# AdaptWing.net
KiCad netlist of a schematic drawn in Altium Designer
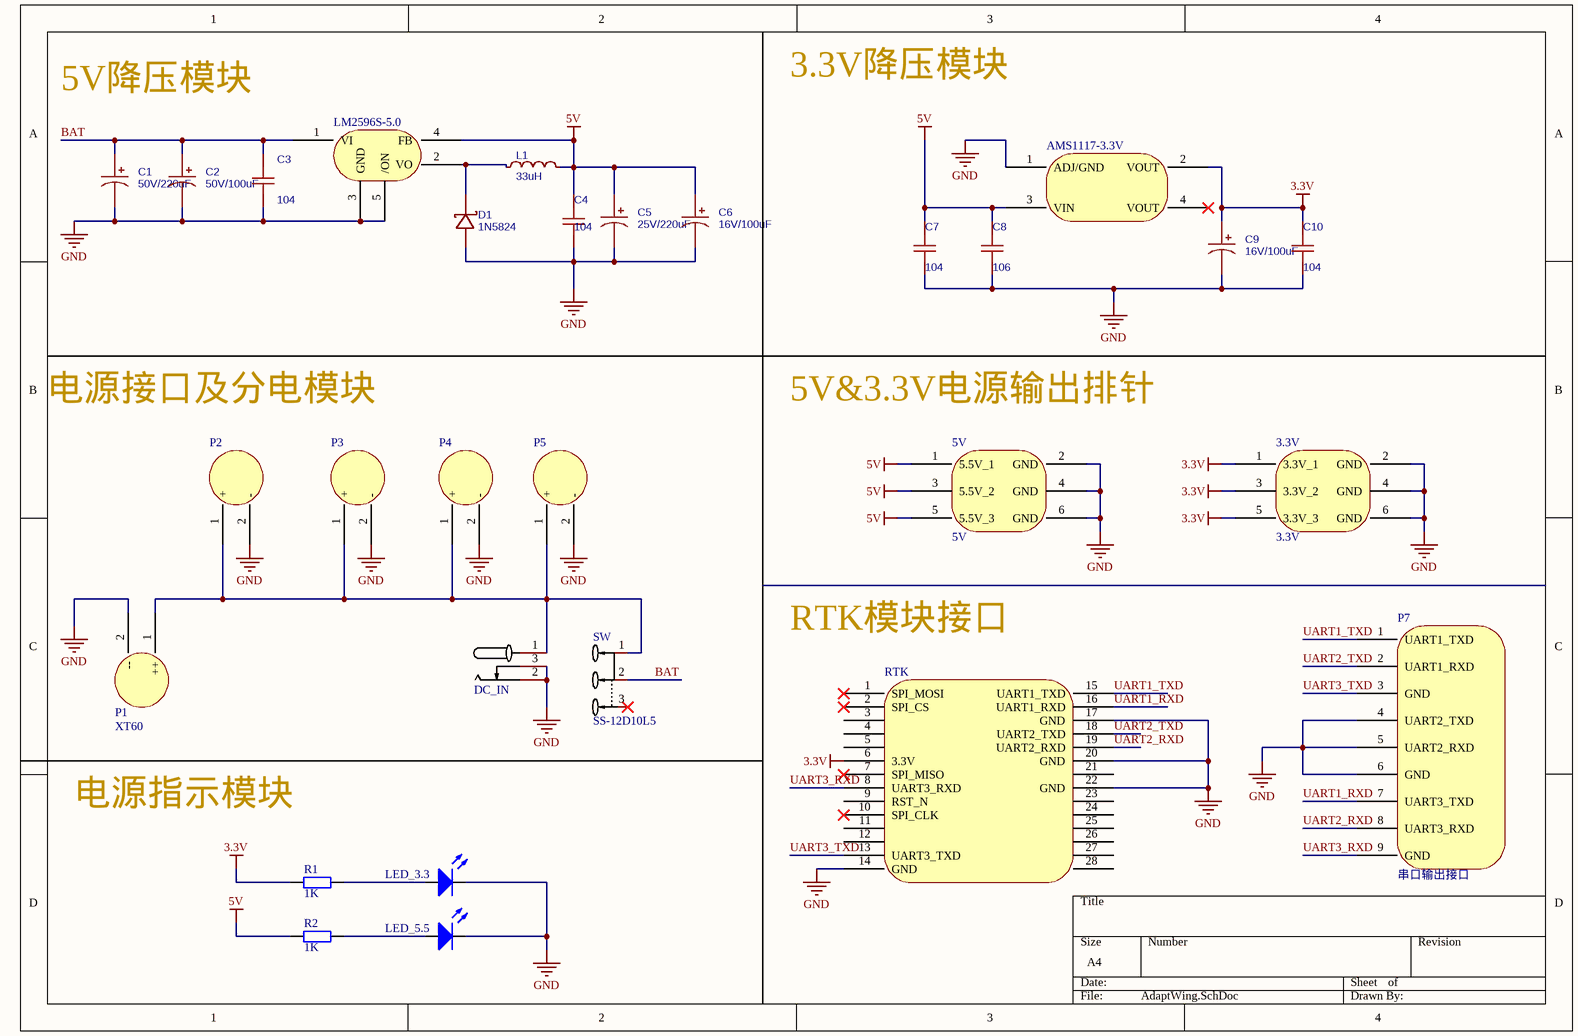
[diagram p0: AdaptWing.SchDoc]

(export (version "E")
  (design (tool "Eeschema 10.0.6"))
  (components
    (comp (ref "3.3V")
      (value "3.3V")
      (footprint "HDR-TH_6P-P2.54-V-M-R2-C3-S2.54-1")
      (libsource (lib "AdaptWing") (part "3.3V"))
    )
    (comp (ref "5V")
      (value "5V")
      (footprint "HDR-TH_6P-P2.54-V-M-R2-C3-S2.54-1")
      (libsource (lib "AdaptWing") (part "5V"))
    )
    (comp (ref "AMS1117-3.3V")
      (value "AMS1117-3.3V")
      (footprint "SOT-223-4_L6.5-W3.5-P2.30-LS7.0-BR")
      (description "3.3V稳压芯片")
      (libsource (lib "AdaptWing") (part "AMS1117-3.3V"))
    )
    (comp (ref "C1")
      (value "50V/220uF")
      (footprint "CAP-SMD_BD8.0-L8.3-W8.3-FD")
      (fields
        (field (name "BOM_SUPPLIER PART") "C525429")
        (field (name "BOM_MANUFACTURER PART") "ECG1KM470F14OTBO")
        (field (name "CONTRIBUTOR") "LCSC")
      )
      (libsource (lib "AdaptWing") (part "50V/220uF"))
    )
    (comp (ref "C2")
      (value "50V/100uF")
      (footprint "CAP-SMD_BD8.0-L8.3-W8.3-FD")
      (fields
        (field (name "BOM_SUPPLIER PART") "C525429")
        (field (name "BOM_MANUFACTURER PART") "ECG1KM470F14OTBO")
        (field (name "CONTRIBUTOR") "LCSC")
      )
      (libsource (lib "AdaptWing") (part "50V/100uF"))
    )
    (comp (ref "C3")
      (value "104")
      (footprint "C0603")
      (fields (field (name "CONTRIBUTOR") "LCEDA_Lib"))
      (libsource (lib "AdaptWing") (part "104"))
    )
    (comp (ref "C4")
      (value "104")
      (footprint "C0603")
      (fields (field (name "CONTRIBUTOR") "LCEDA_Lib"))
      (libsource (lib "AdaptWing") (part "104"))
    )
    (comp (ref "C5")
      (value "25V/220uF")
      (footprint "CAP-SMD_BD6.3-L6.6-W6.6-LS7.4-FD")
      (fields
        (field (name "BOM_SUPPLIER PART") "C525429")
        (field (name "BOM_MANUFACTURER PART") "ECG1KM470F14OTBO")
        (field (name "CONTRIBUTOR") "LCSC")
      )
      (libsource (lib "AdaptWing") (part "25V/220uF"))
    )
    (comp (ref "C6")
      (value "16V/100uF")
      (footprint "CAP-SMD_BD6.3-L6.6-W6.6-FD")
      (description "电解电容")
      (fields
        (field (name "BOM_SUPPLIER PART") "C525429")
        (field (name "BOM_MANUFACTURER PART") "ECG1KM470F14OTBO")
        (field (name "CONTRIBUTOR") "LCSC")
      )
      (libsource (lib "AdaptWing") (part "16V/100uF"))
    )
    (comp (ref "C7")
      (value "104")
      (footprint "C0603")
      (fields (field (name "CONTRIBUTOR") "LCEDA_Lib"))
      (libsource (lib "AdaptWing") (part "104"))
    )
    (comp (ref "C8")
      (value "106")
      (footprint "C0603")
      (fields (field (name "CONTRIBUTOR") "LCEDA_Lib"))
      (libsource (lib "AdaptWing") (part "106"))
    )
    (comp (ref "C9")
      (value "16V/100uF")
      (footprint "CAP-SMD_BD6.3-L6.6-W6.6-FD")
      (description "电解电容")
      (fields
        (field (name "BOM_SUPPLIER PART") "C525429")
        (field (name "BOM_MANUFACTURER PART") "ECG1KM470F14OTBO")
        (field (name "CONTRIBUTOR") "LCSC")
      )
      (libsource (lib "AdaptWing") (part "16V/100uF"))
    )
    (comp (ref "C10")
      (value "104")
      (footprint "C0603")
      (fields (field (name "CONTRIBUTOR") "LCEDA_Lib"))
      (libsource (lib "AdaptWing") (part "104"))
    )
    (comp (ref "D1")
      (value "1N5824")
      (footprint "1N5824")
      (fields (field (name "CONTRIBUTOR") "xuncikulv"))
      (libsource (lib "AdaptWing") (part "1N5824"))
    )
    (comp (ref "DC_IN")
      (value "DC插座")
      (footprint "DC-IN-TH_DC-044-BXXX")
      (libsource (lib "AdaptWing") (part "DC插座"))
    )
    (comp (ref "L1")
      (value "33uH")
      (footprint "1040电感")
      (fields
        (field (name "BOM_SUPPLIER PART") "C268399")
        (field (name "BOM_MANUFACTURER PART") "MPCA-0630-1R0-M")
        (field (name "CONTRIBUTOR") "liuliubilc")
      )
      (libsource (lib "AdaptWing") (part "33uH"))
    )
    (comp (ref "LED_3.3")
      (value "LED_3.3")
      (footprint "0603_LED")
      (description "LED_3.3，使用绿色LED")
      (libsource (lib "AdaptWing") (part "LED_3.3"))
    )
    (comp (ref "LED_5.5")
      (value "LED_5.5")
      (footprint "0603_LED")
      (description "LED_5.5，使用蓝色LED")
      (libsource (lib "AdaptWing") (part "LED_5.5"))
    )
    (comp (ref "LM2596S-5.0")
      (value "LM2596S-5.0")
      (footprint "TO263-5A")
      (description "5V稳压")
      (libsource (lib "AdaptWing") (part "LM2596S-5.0"))
    )
    (comp (ref "P1")
      (value "XT60")
      (footprint "分电焊盘")
      (description "航模电池接口")
      (libsource (lib "AdaptWing") (part "XT60"))
    )
    (comp (ref "P2") (value "分电焊盘") (footprint "分电焊盘") (libsource (lib "AdaptWing") (part "PWR_DIV")))
    (comp (ref "P3") (value "分电焊盘") (footprint "分电焊盘") (libsource (lib "AdaptWing") (part "PWR_DIV")))
    (comp (ref "P4") (value "分电焊盘") (footprint "分电焊盘") (libsource (lib "AdaptWing") (part "PWR_DIV")))
    (comp (ref "P5") (value "分电焊盘") (footprint "分电焊盘") (libsource (lib "AdaptWing") (part "PWR_DIV")))
    (comp (ref "P7")
      (value "串口输出接口")
      (footprint "2.54mm-3×3p")
      (libsource (lib "AdaptWing") (part "2.54mm-3×3p"))
    )
    (comp (ref "R1")
      (value "1K")
      (footprint "0603C")
      (description "Resistor")
      (fields (field (name "PUBLISHER") "Altium Limited"))
      (libsource (lib "AdaptWing") (part "1K"))
    )
    (comp (ref "R2")
      (value "1K")
      (footprint "0603C")
      (description "Resistor")
      (fields (field (name "PUBLISHER") "Altium Limited"))
      (libsource (lib "AdaptWing") (part "1K"))
    )
    (comp (ref "RTK")
      (value "排母2.0mm")
      (footprint "2mm-28pins")
      (libsource (lib "AdaptWing") (part "排母2.0mm"))
    )
    (comp (ref "SW")
      (value "SS-12D10L5")
      (footprint "SW-TH_SS-12D10L5")
      (description "两档滑动开关")
      (fields (field (name "MANUFACTURER") "XKB Connectivity(中国星坤)") (field (name "NAME") "SS-12D10L5"))
      (libsource (lib "AdaptWing") (part "SS-12D10L5"))
    )
  )
  (nets
    (net (code "1") (name "/BAT") (class "Default")
      (node (ref "C1") (pin "1") (pinfunction "1_1") (pintype "passive"))
      (node (ref "C2") (pin "1") (pinfunction "1_1") (pintype "passive"))
      (node (ref "C3") (pin "2") (pinfunction "2_2") (pintype "passive"))
      (node (ref "LM2596S-5.0") (pin "1") (pinfunction "VI_1") (pintype "passive"))
      (node (ref "SW") (pin "2") (pinfunction "2_2") (pintype "passive"))
    )
    (net (code "2") (name "/UART1_RXD") (class "Default")
      (node (ref "P7") (pin "7") (pinfunction "UART3_TXD_7") (pintype "passive"))
      (node (ref "RTK") (pin "16") (pinfunction "UART1_RXD_16") (pintype "passive"))
    )
    (net (code "3") (name "/UART1_TXD") (class "Default")
      (node (ref "P7") (pin "1") (pinfunction "UART1_TXD_1") (pintype "passive"))
      (node (ref "RTK") (pin "15") (pinfunction "UART1_TXD_15") (pintype "passive"))
    )
    (net (code "4") (name "/UART2_RXD") (class "Default")
      (node (ref "P7") (pin "8") (pinfunction "UART3_RXD_8") (pintype "passive"))
      (node (ref "RTK") (pin "19") (pinfunction "UART2_RXD_19") (pintype "passive"))
    )
    (net (code "5") (name "/UART2_TXD") (class "Default")
      (node (ref "P7") (pin "2") (pinfunction "UART1_RXD_2") (pintype "passive"))
      (node (ref "RTK") (pin "18") (pinfunction "UART2_TXD_18") (pintype "passive"))
    )
    (net (code "6") (name "/UART3_RXD") (class "Default")
      (node (ref "P7") (pin "9") (pinfunction "GND_9") (pintype "passive"))
      (node (ref "RTK") (pin "8") (pinfunction "UART3_RXD_8") (pintype "passive"))
    )
    (net (code "7") (name "/UART3_TXD") (class "Default")
      (node (ref "P7") (pin "3") (pinfunction "GND_3") (pintype "passive"))
      (node (ref "RTK") (pin "13") (pinfunction "UART3_TXD_13") (pintype "passive"))
    )
    (net (code "8") (name "3.3V") (class "Default")
      (node (ref "3.3V") (pin "1") (pinfunction "3.3V_1_1") (pintype "passive"))
      (node (ref "3.3V") (pin "3") (pinfunction "3.3V_2_3") (pintype "passive"))
      (node (ref "3.3V") (pin "5") (pinfunction "3.3V_3_5") (pintype "passive"))
      (node (ref "AMS1117-3.3V") (pin "2") (pinfunction "VOUT_2") (pintype "passive"))
      (node (ref "C10") (pin "2") (pinfunction "2_2") (pintype "passive"))
      (node (ref "C9") (pin "1") (pinfunction "1_1") (pintype "passive"))
      (node (ref "R1") (pin "1") (pinfunction "1_1") (pintype "passive"))
      (node (ref "RTK") (pin "6") (pinfunction "3.3V_6") (pintype "passive"))
    )
    (net (code "9") (name "5V") (class "Default")
      (node (ref "5V") (pin "1") (pinfunction "5.5V_1_1") (pintype "passive"))
      (node (ref "5V") (pin "3") (pinfunction "5.5V_2_3") (pintype "passive"))
      (node (ref "5V") (pin "5") (pinfunction "5.5V_3_5") (pintype "passive"))
      (node (ref "AMS1117-3.3V") (pin "3") (pinfunction "VIN_3") (pintype "passive"))
      (node (ref "C4") (pin "2") (pinfunction "2_2") (pintype "passive"))
      (node (ref "C5") (pin "1") (pinfunction "1_1") (pintype "passive"))
      (node (ref "C6") (pin "1") (pinfunction "1_1") (pintype "passive"))
      (node (ref "C7") (pin "2") (pinfunction "2_2") (pintype "passive"))
      (node (ref "C8") (pin "2") (pinfunction "2_2") (pintype "passive"))
      (node (ref "L1") (pin "2") (pinfunction "2_2") (pintype "passive"))
      (node (ref "LM2596S-5.0") (pin "4") (pinfunction "FB_4") (pintype "passive"))
      (node (ref "R2") (pin "1") (pinfunction "1_1") (pintype "passive"))
    )
    (net (code "10") (name "GND") (class "Default")
      (node (ref "3.3V") (pin "2") (pinfunction "GND_2") (pintype "passive"))
      (node (ref "3.3V") (pin "4") (pinfunction "GND_4") (pintype "passive"))
      (node (ref "3.3V") (pin "6") (pinfunction "GND_6") (pintype "passive"))
      (node (ref "5V") (pin "2") (pinfunction "GND_2") (pintype "passive"))
      (node (ref "5V") (pin "4") (pinfunction "GND_4") (pintype "passive"))
      (node (ref "5V") (pin "6") (pinfunction "GND_6") (pintype "passive"))
      (node (ref "AMS1117-3.3V") (pin "1") (pinfunction "ADJ/GND_1") (pintype "passive"))
      (node (ref "C1") (pin "2") (pinfunction "2_2") (pintype "passive"))
      (node (ref "C10") (pin "1") (pinfunction "1_1") (pintype "passive"))
      (node (ref "C2") (pin "2") (pinfunction "2_2") (pintype "passive"))
      (node (ref "C3") (pin "1") (pinfunction "1_1") (pintype "passive"))
      (node (ref "C4") (pin "1") (pinfunction "1_1") (pintype "passive"))
      (node (ref "C5") (pin "2") (pinfunction "2_2") (pintype "passive"))
      (node (ref "C6") (pin "2") (pinfunction "2_2") (pintype "passive"))
      (node (ref "C7") (pin "1") (pinfunction "1_1") (pintype "passive"))
      (node (ref "C8") (pin "1") (pinfunction "1_1") (pintype "passive"))
      (node (ref "C9") (pin "2") (pinfunction "2_2") (pintype "passive"))
      (node (ref "D1") (pin "2") (pinfunction "A_2") (pintype "passive"))
      (node (ref "DC_IN") (pin "2") (pinfunction "GND_2") (pintype "passive"))
      (node (ref "DC_IN") (pin "3") (pinfunction "GND_3") (pintype "passive"))
      (node (ref "LED_3.3") (pin "2") (pinfunction "K_2") (pintype "passive"))
      (node (ref "LED_5.5") (pin "2") (pinfunction "K_2") (pintype "passive"))
      (node (ref "LM2596S-5.0") (pin "3") (pinfunction "GND_3") (pintype "passive"))
      (node (ref "LM2596S-5.0") (pin "5") (pinfunction "/ON_5") (pintype "passive"))
      (node (ref "P1") (pin "2") (pinfunction "--_2") (pintype "passive"))
      (node (ref "P2") (pin "2") (pinfunction "-_2") (pintype "passive"))
      (node (ref "P3") (pin "2") (pinfunction "-_2") (pintype "passive"))
      (node (ref "P4") (pin "2") (pinfunction "-_2") (pintype "passive"))
      (node (ref "P5") (pin "2") (pinfunction "-_2") (pintype "passive"))
      (node (ref "P7") (pin "4") (pinfunction "UART2_TXD_4") (pintype "passive"))
      (node (ref "P7") (pin "5") (pinfunction "UART2_RXD_5") (pintype "passive"))
      (node (ref "P7") (pin "6") (pinfunction "GND_6") (pintype "passive"))
      (node (ref "RTK") (pin "14") (pinfunction "GND_14") (pintype "passive"))
      (node (ref "RTK") (pin "17") (pinfunction "GND_17") (pintype "passive"))
      (node (ref "RTK") (pin "20") (pinfunction "GND_20") (pintype "passive"))
      (node (ref "RTK") (pin "22") (pinfunction "GND_22") (pintype "passive"))
    )
    (net (code "11") (name "Net-(D1-C)") (class "Default")
      (node (ref "D1") (pin "1") (pinfunction "C_1") (pintype "passive"))
      (node (ref "L1") (pin "1") (pinfunction "1_1") (pintype "passive"))
      (node (ref "LM2596S-5.0") (pin "2") (pinfunction "VO_2") (pintype "passive"))
    )
    (net (code "12") (name "Net-(DC_IN-pwr)") (class "Default")
      (node (ref "DC_IN") (pin "1") (pinfunction "pwr_1") (pintype "passive"))
      (node (ref "P1") (pin "1") (pinfunction "++_1") (pintype "passive"))
      (node (ref "P2") (pin "1") (pinfunction "+_1") (pintype "passive"))
      (node (ref "P3") (pin "1") (pinfunction "+_1") (pintype "passive"))
      (node (ref "P4") (pin "1") (pinfunction "+_1") (pintype "passive"))
      (node (ref "P5") (pin "1") (pinfunction "+_1") (pintype "passive"))
      (node (ref "SW") (pin "1") (pinfunction "1_1") (pintype "passive"))
    )
    (net (code "13") (name "Net-(LED_3.3-A)") (class "Default")
      (node (ref "LED_3.3") (pin "1") (pinfunction "A_1") (pintype "passive"))
      (node (ref "R1") (pin "2") (pinfunction "2_2") (pintype "passive"))
    )
    (net (code "14") (name "Net-(LED_5.5-A)") (class "Default")
      (node (ref "LED_5.5") (pin "1") (pinfunction "A_1") (pintype "passive"))
      (node (ref "R2") (pin "2") (pinfunction "2_2") (pintype "passive"))
    )
    (net (code "15") (name "unconnected-(AMS1117-3.3V-VOUT-Pad4)") (class "Default")
      (node (ref "AMS1117-3.3V") (pin "4") (pinfunction "VOUT_4") (pintype "passive+no_connect"))
    )
    (net (code "16") (name "unconnected-(RTK-Pad3)") (class "Default")
      (node (ref "RTK") (pin "3") (pintype "passive"))
    )
    (net (code "17") (name "unconnected-(RTK-Pad4)") (class "Default")
      (node (ref "RTK") (pin "4") (pintype "passive"))
    )
    (net (code "18") (name "unconnected-(RTK-Pad5)") (class "Default")
      (node (ref "RTK") (pin "5") (pintype "passive"))
    )
    (net (code "19") (name "unconnected-(RTK-Pad11)") (class "Default")
      (node (ref "RTK") (pin "11") (pintype "passive"))
    )
    (net (code "20") (name "unconnected-(RTK-Pad12)") (class "Default")
      (node (ref "RTK") (pin "12") (pintype "passive"))
    )
    (net (code "21") (name "unconnected-(RTK-Pad21)") (class "Default")
      (node (ref "RTK") (pin "21") (pintype "passive"))
    )
    (net (code "22") (name "unconnected-(RTK-Pad23)") (class "Default")
      (node (ref "RTK") (pin "23") (pintype "passive"))
    )
    (net (code "23") (name "unconnected-(RTK-Pad24)") (class "Default")
      (node (ref "RTK") (pin "24") (pintype "passive"))
    )
    (net (code "24") (name "unconnected-(RTK-Pad25)") (class "Default")
      (node (ref "RTK") (pin "25") (pintype "passive"))
    )
    (net (code "25") (name "unconnected-(RTK-Pad26)") (class "Default")
      (node (ref "RTK") (pin "26") (pintype "passive"))
    )
    (net (code "26") (name "unconnected-(RTK-Pad27)") (class "Default")
      (node (ref "RTK") (pin "27") (pintype "passive"))
    )
    (net (code "27") (name "unconnected-(RTK-Pad28)") (class "Default")
      (node (ref "RTK") (pin "28") (pintype "passive"))
    )
    (net (code "28") (name "unconnected-(RTK-RST_N-Pad9)") (class "Default")
      (node (ref "RTK") (pin "9") (pinfunction "RST_N_9") (pintype "passive"))
    )
    (net (code "29") (name "unconnected-(RTK-SPI_CLK-Pad10)") (class "Default")
      (node (ref "RTK") (pin "10") (pinfunction "SPI_CLK_10") (pintype "passive+no_connect"))
    )
    (net (code "30") (name "unconnected-(RTK-SPI_CS-Pad2)") (class "Default")
      (node (ref "RTK") (pin "2") (pinfunction "SPI_CS_2") (pintype "passive+no_connect"))
    )
    (net (code "31") (name "unconnected-(RTK-SPI_MISO-Pad7)") (class "Default")
      (node (ref "RTK") (pin "7") (pinfunction "SPI_MISO_7") (pintype "passive+no_connect"))
    )
    (net (code "32") (name "unconnected-(RTK-SPI_MOSI-Pad1)") (class "Default")
      (node (ref "RTK") (pin "1") (pinfunction "SPI_MOSI_1") (pintype "passive+no_connect"))
    )
    (net (code "33") (name "unconnected-(SW-Pad3)") (class "Default")
      (node (ref "SW") (pin "3") (pinfunction "3_3") (pintype "passive+no_connect"))
    )
  )
)
